# NeoDigito_Mini_X.net
KiCad netlist of a schematic drawn in EAGLE
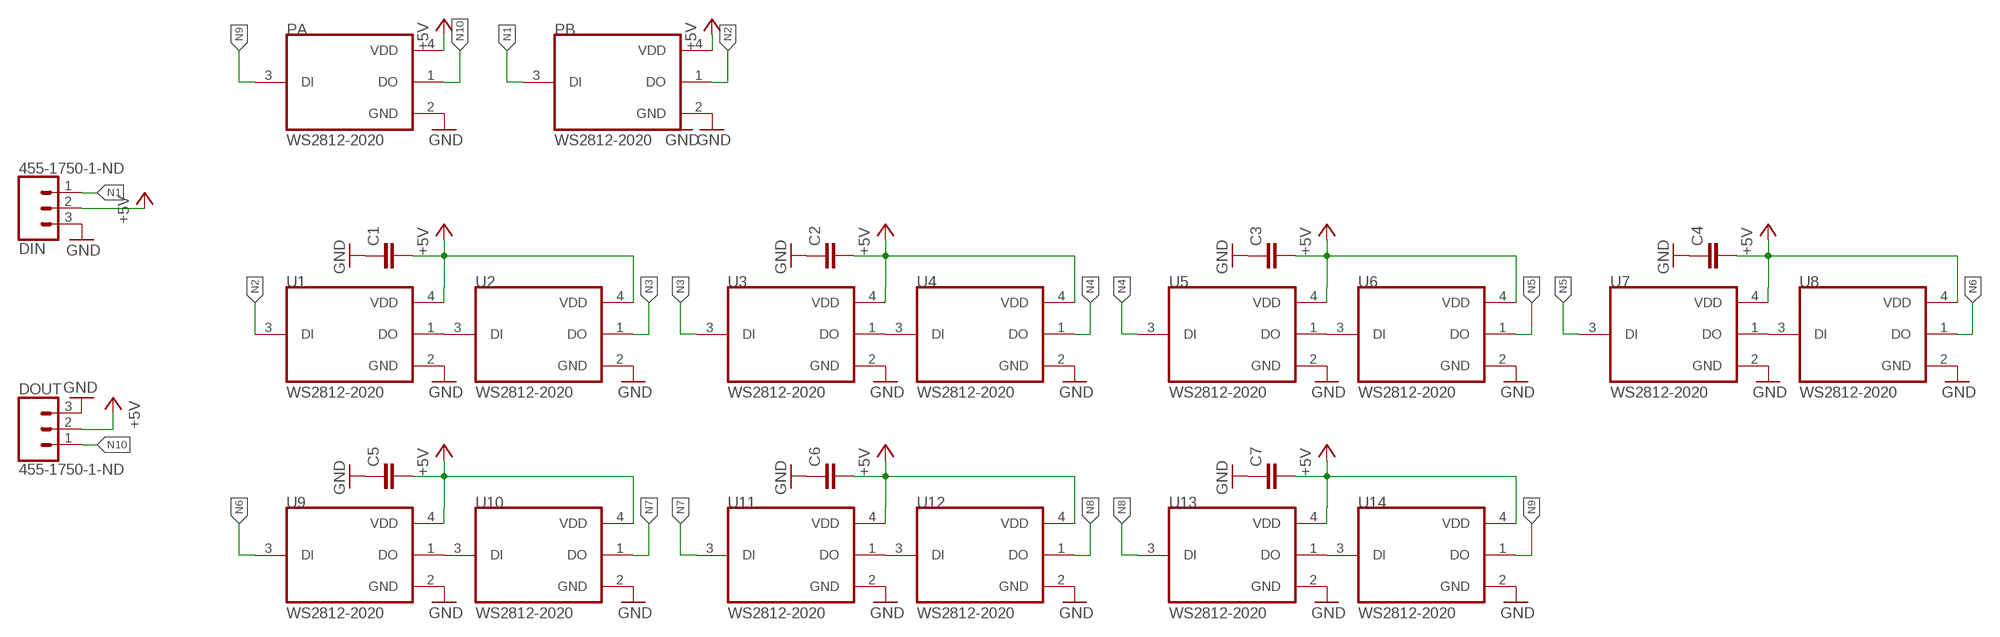
[diagram p0: schematic, sheet 1]

(export (version "E")
  (design (tool "Eeschema 10.0.6"))
  (components
    (comp (ref "C1")
      (value "C-EUC0805")
      (footprint "eagle-import:C0805")
      (libsource (lib "eagle-import") (part "C-EUC0805"))
    )
    (comp (ref "C2")
      (value "C-EUC0805")
      (footprint "eagle-import:C0805")
      (libsource (lib "eagle-import") (part "C-EUC0805"))
    )
    (comp (ref "C3")
      (value "C-EUC0805")
      (footprint "eagle-import:C0805")
      (libsource (lib "eagle-import") (part "C-EUC0805"))
    )
    (comp (ref "C4")
      (value "C-EUC0805")
      (footprint "eagle-import:C0805")
      (libsource (lib "eagle-import") (part "C-EUC0805"))
    )
    (comp (ref "C5")
      (value "C-EUC0805")
      (footprint "eagle-import:C0805")
      (libsource (lib "eagle-import") (part "C-EUC0805"))
    )
    (comp (ref "C6")
      (value "C-EUC0805")
      (footprint "eagle-import:C0805")
      (libsource (lib "eagle-import") (part "C-EUC0805"))
    )
    (comp (ref "C7")
      (value "C-EUC0805")
      (footprint "eagle-import:C0805")
      (libsource (lib "eagle-import") (part "C-EUC0805"))
    )
    (comp (ref "DIN")
      (value "455-1750-1-ND")
      (footprint "eagle-import:1X03")
      (libsource (lib "eagle-import") (part "CONN_03"))
    )
    (comp (ref "DOUT")
      (value "455-1750-1-ND")
      (footprint "eagle-import:1X03")
      (libsource (lib "eagle-import") (part "CONN_03"))
    )
    (comp (ref "PA")
      (value "WS2812-2020")
      (footprint "eagle-import:LED_WS2812-2020")
      (fields (field (name "MF") "Worldsemi"))
      (libsource (lib "eagle-import") (part "WS2812-2020"))
    )
    (comp (ref "PB")
      (value "WS2812-2020")
      (footprint "eagle-import:LED_WS2812-2020")
      (fields (field (name "MF") "Worldsemi"))
      (libsource (lib "eagle-import") (part "WS2812-2020"))
    )
    (comp (ref "U1")
      (value "WS2812-2020")
      (footprint "eagle-import:LED_WS2812-2020")
      (fields (field (name "MF") "Worldsemi"))
      (libsource (lib "eagle-import") (part "WS2812-2020"))
    )
    (comp (ref "U2")
      (value "WS2812-2020")
      (footprint "eagle-import:LED_WS2812-2020")
      (fields (field (name "MF") "Worldsemi"))
      (libsource (lib "eagle-import") (part "WS2812-2020"))
    )
    (comp (ref "U3")
      (value "WS2812-2020")
      (footprint "eagle-import:LED_WS2812-2020")
      (fields (field (name "MF") "Worldsemi"))
      (libsource (lib "eagle-import") (part "WS2812-2020"))
    )
    (comp (ref "U4")
      (value "WS2812-2020")
      (footprint "eagle-import:LED_WS2812-2020")
      (fields (field (name "MF") "Worldsemi"))
      (libsource (lib "eagle-import") (part "WS2812-2020"))
    )
    (comp (ref "U5")
      (value "WS2812-2020")
      (footprint "eagle-import:LED_WS2812-2020")
      (fields (field (name "MF") "Worldsemi"))
      (libsource (lib "eagle-import") (part "WS2812-2020"))
    )
    (comp (ref "U6")
      (value "WS2812-2020")
      (footprint "eagle-import:LED_WS2812-2020")
      (fields (field (name "MF") "Worldsemi"))
      (libsource (lib "eagle-import") (part "WS2812-2020"))
    )
    (comp (ref "U7")
      (value "WS2812-2020")
      (footprint "eagle-import:LED_WS2812-2020")
      (fields (field (name "MF") "Worldsemi"))
      (libsource (lib "eagle-import") (part "WS2812-2020"))
    )
    (comp (ref "U8")
      (value "WS2812-2020")
      (footprint "eagle-import:LED_WS2812-2020")
      (fields (field (name "MF") "Worldsemi"))
      (libsource (lib "eagle-import") (part "WS2812-2020"))
    )
    (comp (ref "U9")
      (value "WS2812-2020")
      (footprint "eagle-import:LED_WS2812-2020")
      (fields (field (name "MF") "Worldsemi"))
      (libsource (lib "eagle-import") (part "WS2812-2020"))
    )
    (comp (ref "U10")
      (value "WS2812-2020")
      (footprint "eagle-import:LED_WS2812-2020")
      (fields (field (name "MF") "Worldsemi"))
      (libsource (lib "eagle-import") (part "WS2812-2020"))
    )
    (comp (ref "U11")
      (value "WS2812-2020")
      (footprint "eagle-import:LED_WS2812-2020")
      (fields (field (name "MF") "Worldsemi"))
      (libsource (lib "eagle-import") (part "WS2812-2020"))
    )
    (comp (ref "U12")
      (value "WS2812-2020")
      (footprint "eagle-import:LED_WS2812-2020")
      (fields (field (name "MF") "Worldsemi"))
      (libsource (lib "eagle-import") (part "WS2812-2020"))
    )
    (comp (ref "U13")
      (value "WS2812-2020")
      (footprint "eagle-import:LED_WS2812-2020")
      (fields (field (name "MF") "Worldsemi"))
      (libsource (lib "eagle-import") (part "WS2812-2020"))
    )
    (comp (ref "U14")
      (value "WS2812-2020")
      (footprint "eagle-import:LED_WS2812-2020")
      (fields (field (name "MF") "Worldsemi"))
      (libsource (lib "eagle-import") (part "WS2812-2020"))
    )
  )
  (nets
    (net (code "1") (name "+5V") (class "Default")
      (node (ref "C1") (pin "2") (pinfunction "2_2") (pintype "passive"))
      (node (ref "C2") (pin "2") (pinfunction "2_2") (pintype "passive"))
      (node (ref "C3") (pin "2") (pinfunction "2_2") (pintype "passive"))
      (node (ref "C4") (pin "2") (pinfunction "2_2") (pintype "passive"))
      (node (ref "C5") (pin "2") (pinfunction "2_2") (pintype "passive"))
      (node (ref "C6") (pin "2") (pinfunction "2_2") (pintype "passive"))
      (node (ref "C7") (pin "2") (pinfunction "2_2") (pintype "passive"))
      (node (ref "DIN") (pin "2") (pinfunction "2_2") (pintype "passive"))
      (node (ref "DOUT") (pin "2") (pinfunction "2_2") (pintype "passive"))
      (node (ref "PA") (pin "4") (pinfunction "VDD_4") (pintype "power_in"))
      (node (ref "PB") (pin "4") (pinfunction "VDD_4") (pintype "power_in"))
      (node (ref "U1") (pin "4") (pinfunction "VDD_4") (pintype "power_in"))
      (node (ref "U10") (pin "4") (pinfunction "VDD_4") (pintype "power_in"))
      (node (ref "U11") (pin "4") (pinfunction "VDD_4") (pintype "power_in"))
      (node (ref "U12") (pin "4") (pinfunction "VDD_4") (pintype "power_in"))
      (node (ref "U13") (pin "4") (pinfunction "VDD_4") (pintype "power_in"))
      (node (ref "U14") (pin "4") (pinfunction "VDD_4") (pintype "power_in"))
      (node (ref "U2") (pin "4") (pinfunction "VDD_4") (pintype "power_in"))
      (node (ref "U3") (pin "4") (pinfunction "VDD_4") (pintype "power_in"))
      (node (ref "U4") (pin "4") (pinfunction "VDD_4") (pintype "power_in"))
      (node (ref "U5") (pin "4") (pinfunction "VDD_4") (pintype "power_in"))
      (node (ref "U6") (pin "4") (pinfunction "VDD_4") (pintype "power_in"))
      (node (ref "U7") (pin "4") (pinfunction "VDD_4") (pintype "power_in"))
      (node (ref "U8") (pin "4") (pinfunction "VDD_4") (pintype "power_in"))
      (node (ref "U9") (pin "4") (pinfunction "VDD_4") (pintype "power_in"))
    )
    (net (code "2") (name "GND") (class "Default")
      (node (ref "C1") (pin "1") (pinfunction "1_1") (pintype "passive"))
      (node (ref "C2") (pin "1") (pinfunction "1_1") (pintype "passive"))
      (node (ref "C3") (pin "1") (pinfunction "1_1") (pintype "passive"))
      (node (ref "C4") (pin "1") (pinfunction "1_1") (pintype "passive"))
      (node (ref "C5") (pin "1") (pinfunction "1_1") (pintype "passive"))
      (node (ref "C6") (pin "1") (pinfunction "1_1") (pintype "passive"))
      (node (ref "C7") (pin "1") (pinfunction "1_1") (pintype "passive"))
      (node (ref "DIN") (pin "3") (pinfunction "3_3") (pintype "passive"))
      (node (ref "DOUT") (pin "3") (pinfunction "3_3") (pintype "passive"))
      (node (ref "PA") (pin "2") (pinfunction "GND_2") (pintype "power_in"))
      (node (ref "PB") (pin "2") (pinfunction "GND_2") (pintype "power_in"))
      (node (ref "U1") (pin "2") (pinfunction "GND_2") (pintype "power_in"))
      (node (ref "U10") (pin "2") (pinfunction "GND_2") (pintype "power_in"))
      (node (ref "U11") (pin "2") (pinfunction "GND_2") (pintype "power_in"))
      (node (ref "U12") (pin "2") (pinfunction "GND_2") (pintype "power_in"))
      (node (ref "U13") (pin "2") (pinfunction "GND_2") (pintype "power_in"))
      (node (ref "U14") (pin "2") (pinfunction "GND_2") (pintype "power_in"))
      (node (ref "U2") (pin "2") (pinfunction "GND_2") (pintype "power_in"))
      (node (ref "U3") (pin "2") (pinfunction "GND_2") (pintype "power_in"))
      (node (ref "U4") (pin "2") (pinfunction "GND_2") (pintype "power_in"))
      (node (ref "U5") (pin "2") (pinfunction "GND_2") (pintype "power_in"))
      (node (ref "U6") (pin "2") (pinfunction "GND_2") (pintype "power_in"))
      (node (ref "U7") (pin "2") (pinfunction "GND_2") (pintype "power_in"))
      (node (ref "U8") (pin "2") (pinfunction "GND_2") (pintype "power_in"))
      (node (ref "U9") (pin "2") (pinfunction "GND_2") (pintype "power_in"))
    )
    (net (code "3") (name "N1") (class "Default")
      (node (ref "DIN") (pin "1") (pinfunction "1_1") (pintype "passive"))
      (node (ref "PB") (pin "3") (pinfunction "DI_3") (pintype "input"))
    )
    (net (code "4") (name "N2") (class "Default")
      (node (ref "PB") (pin "1") (pinfunction "DO_1") (pintype "output"))
      (node (ref "U1") (pin "3") (pinfunction "DI_3") (pintype "input"))
    )
    (net (code "5") (name "N3") (class "Default")
      (node (ref "U2") (pin "1") (pinfunction "DO_1") (pintype "output"))
      (node (ref "U3") (pin "3") (pinfunction "DI_3") (pintype "input"))
    )
    (net (code "6") (name "N4") (class "Default")
      (node (ref "U4") (pin "1") (pinfunction "DO_1") (pintype "output"))
      (node (ref "U5") (pin "3") (pinfunction "DI_3") (pintype "input"))
    )
    (net (code "7") (name "N5") (class "Default")
      (node (ref "U6") (pin "1") (pinfunction "DO_1") (pintype "output"))
      (node (ref "U7") (pin "3") (pinfunction "DI_3") (pintype "input"))
    )
    (net (code "8") (name "N6") (class "Default")
      (node (ref "U8") (pin "1") (pinfunction "DO_1") (pintype "output"))
      (node (ref "U9") (pin "3") (pinfunction "DI_3") (pintype "input"))
    )
    (net (code "9") (name "N7") (class "Default")
      (node (ref "U10") (pin "1") (pinfunction "DO_1") (pintype "output"))
      (node (ref "U11") (pin "3") (pinfunction "DI_3") (pintype "input"))
    )
    (net (code "10") (name "N8") (class "Default")
      (node (ref "U12") (pin "1") (pinfunction "DO_1") (pintype "output"))
      (node (ref "U13") (pin "3") (pinfunction "DI_3") (pintype "input"))
    )
    (net (code "11") (name "N9") (class "Default")
      (node (ref "PA") (pin "3") (pinfunction "DI_3") (pintype "input"))
      (node (ref "U14") (pin "1") (pinfunction "DO_1") (pintype "output"))
    )
    (net (code "12") (name "N10") (class "Default")
      (node (ref "DOUT") (pin "1") (pinfunction "1_1") (pintype "passive"))
      (node (ref "PA") (pin "1") (pinfunction "DO_1") (pintype "output"))
    )
    (net (code "13") (name "Net-(U1-DO)") (class "Default")
      (node (ref "U1") (pin "1") (pinfunction "DO_1") (pintype "output"))
      (node (ref "U2") (pin "3") (pinfunction "DI_3") (pintype "input"))
    )
    (net (code "14") (name "Net-(U3-DO)") (class "Default")
      (node (ref "U3") (pin "1") (pinfunction "DO_1") (pintype "output"))
      (node (ref "U4") (pin "3") (pinfunction "DI_3") (pintype "input"))
    )
    (net (code "15") (name "Net-(U5-DO)") (class "Default")
      (node (ref "U5") (pin "1") (pinfunction "DO_1") (pintype "output"))
      (node (ref "U6") (pin "3") (pinfunction "DI_3") (pintype "input"))
    )
    (net (code "16") (name "Net-(U7-DO)") (class "Default")
      (node (ref "U7") (pin "1") (pinfunction "DO_1") (pintype "output"))
      (node (ref "U8") (pin "3") (pinfunction "DI_3") (pintype "input"))
    )
    (net (code "17") (name "Net-(U10-DI)") (class "Default")
      (node (ref "U10") (pin "3") (pinfunction "DI_3") (pintype "input"))
      (node (ref "U9") (pin "1") (pinfunction "DO_1") (pintype "output"))
    )
    (net (code "18") (name "Net-(U11-DO)") (class "Default")
      (node (ref "U11") (pin "1") (pinfunction "DO_1") (pintype "output"))
      (node (ref "U12") (pin "3") (pinfunction "DI_3") (pintype "input"))
    )
    (net (code "19") (name "Net-(U13-DO)") (class "Default")
      (node (ref "U13") (pin "1") (pinfunction "DO_1") (pintype "output"))
      (node (ref "U14") (pin "3") (pinfunction "DI_3") (pintype "input"))
    )
  )
)
